# electron_v012.net
KiCad netlist of a schematic drawn in EAGLE
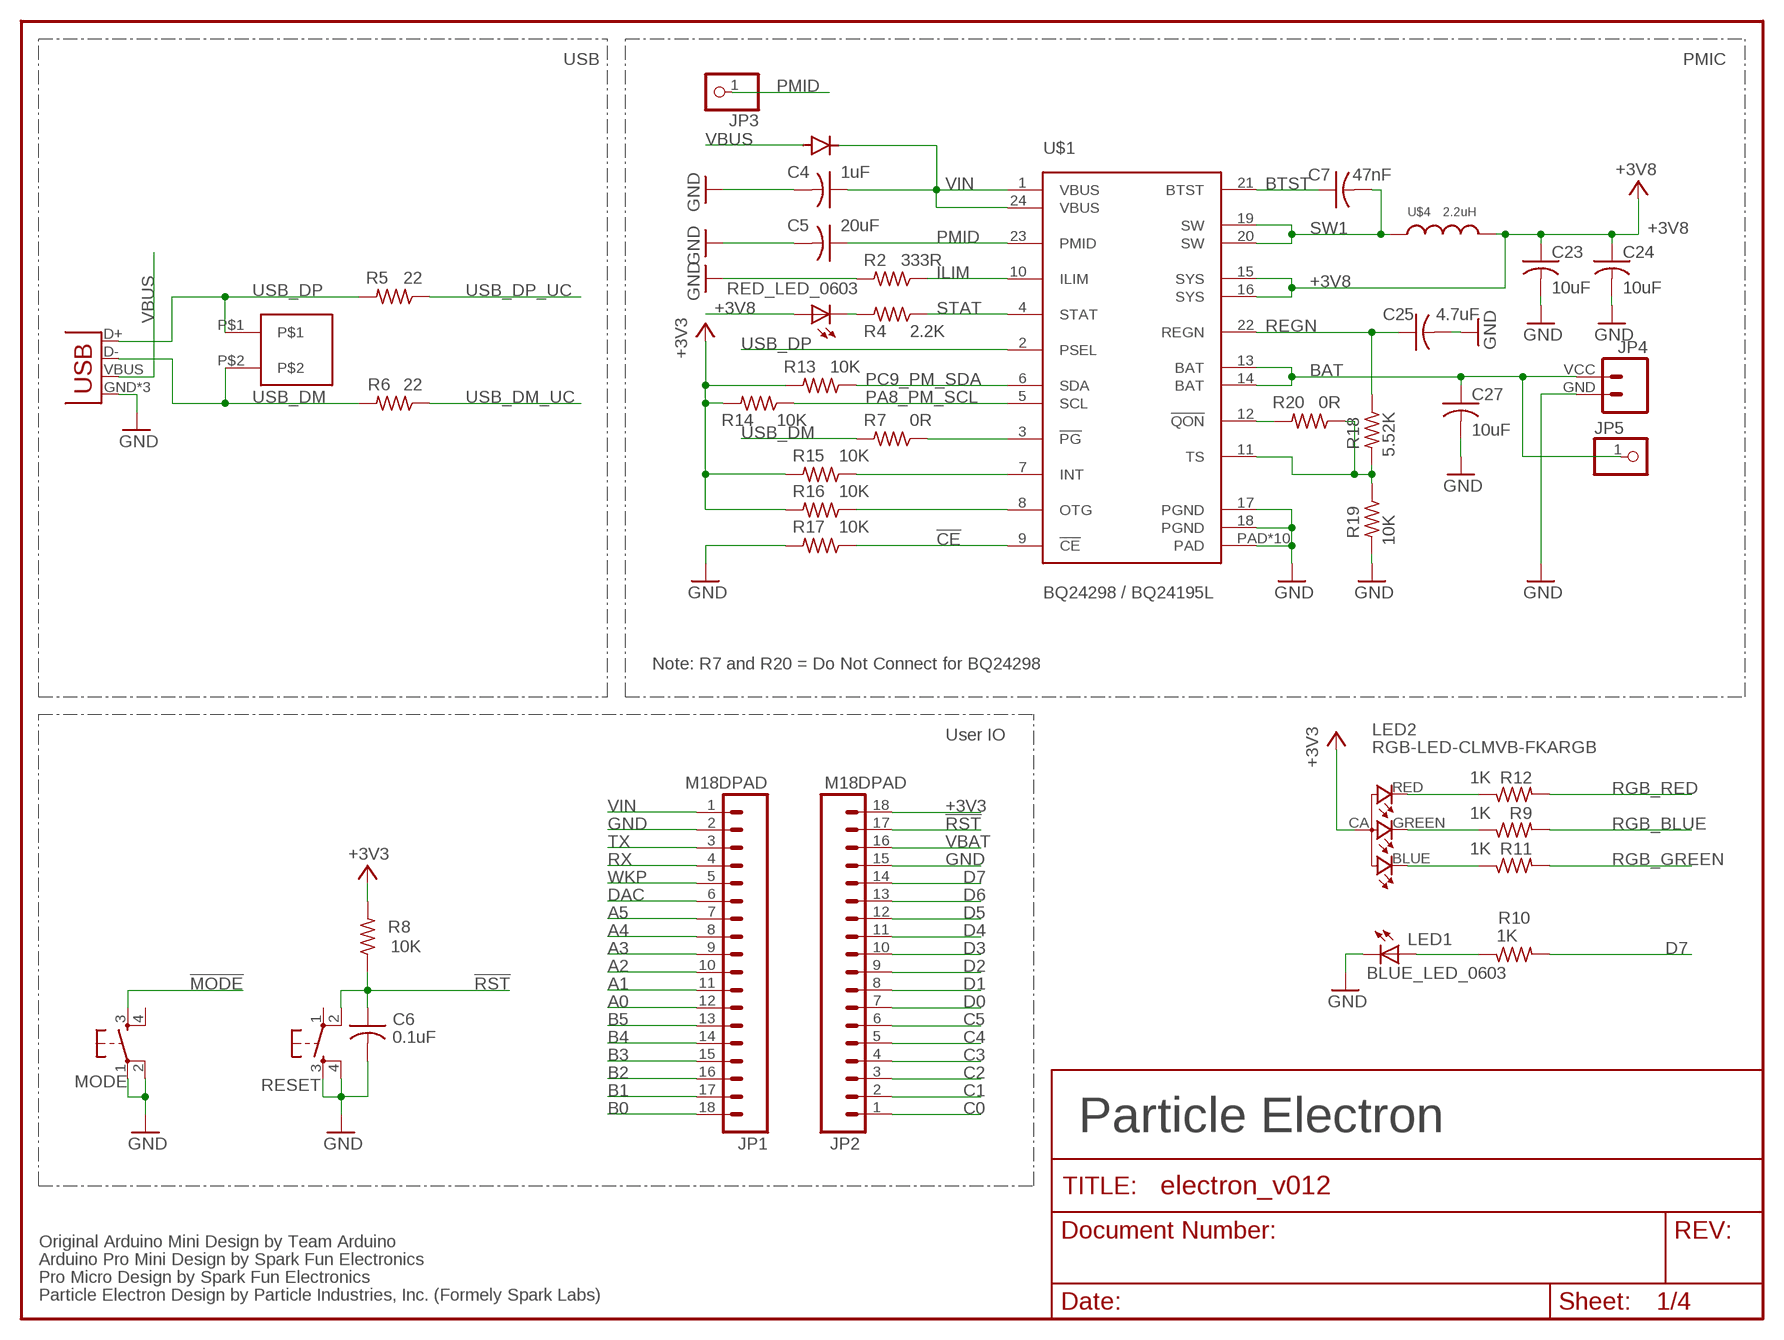
[diagram p0: schematic, sheet 1]
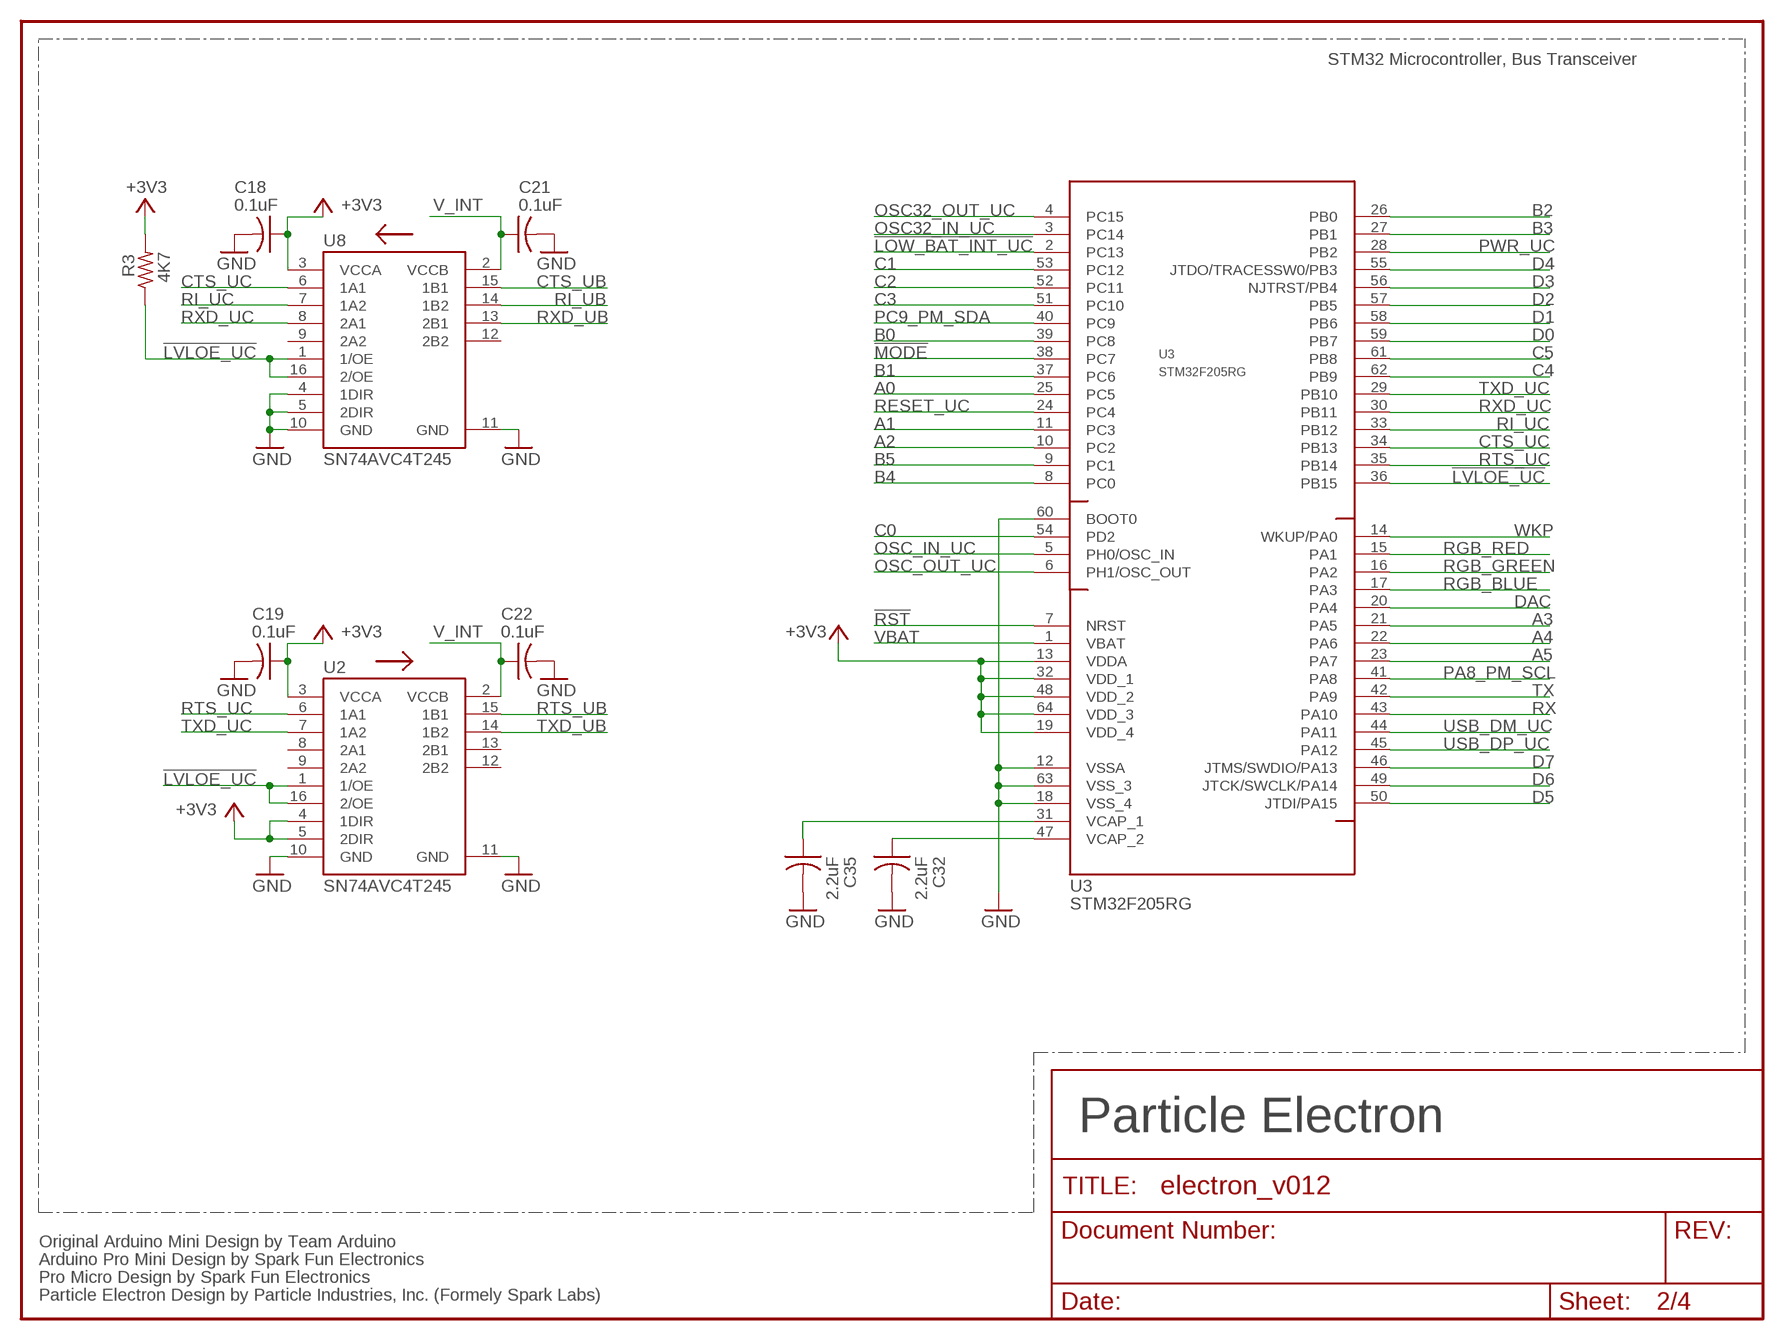
[diagram p1: schematic, sheet 2]
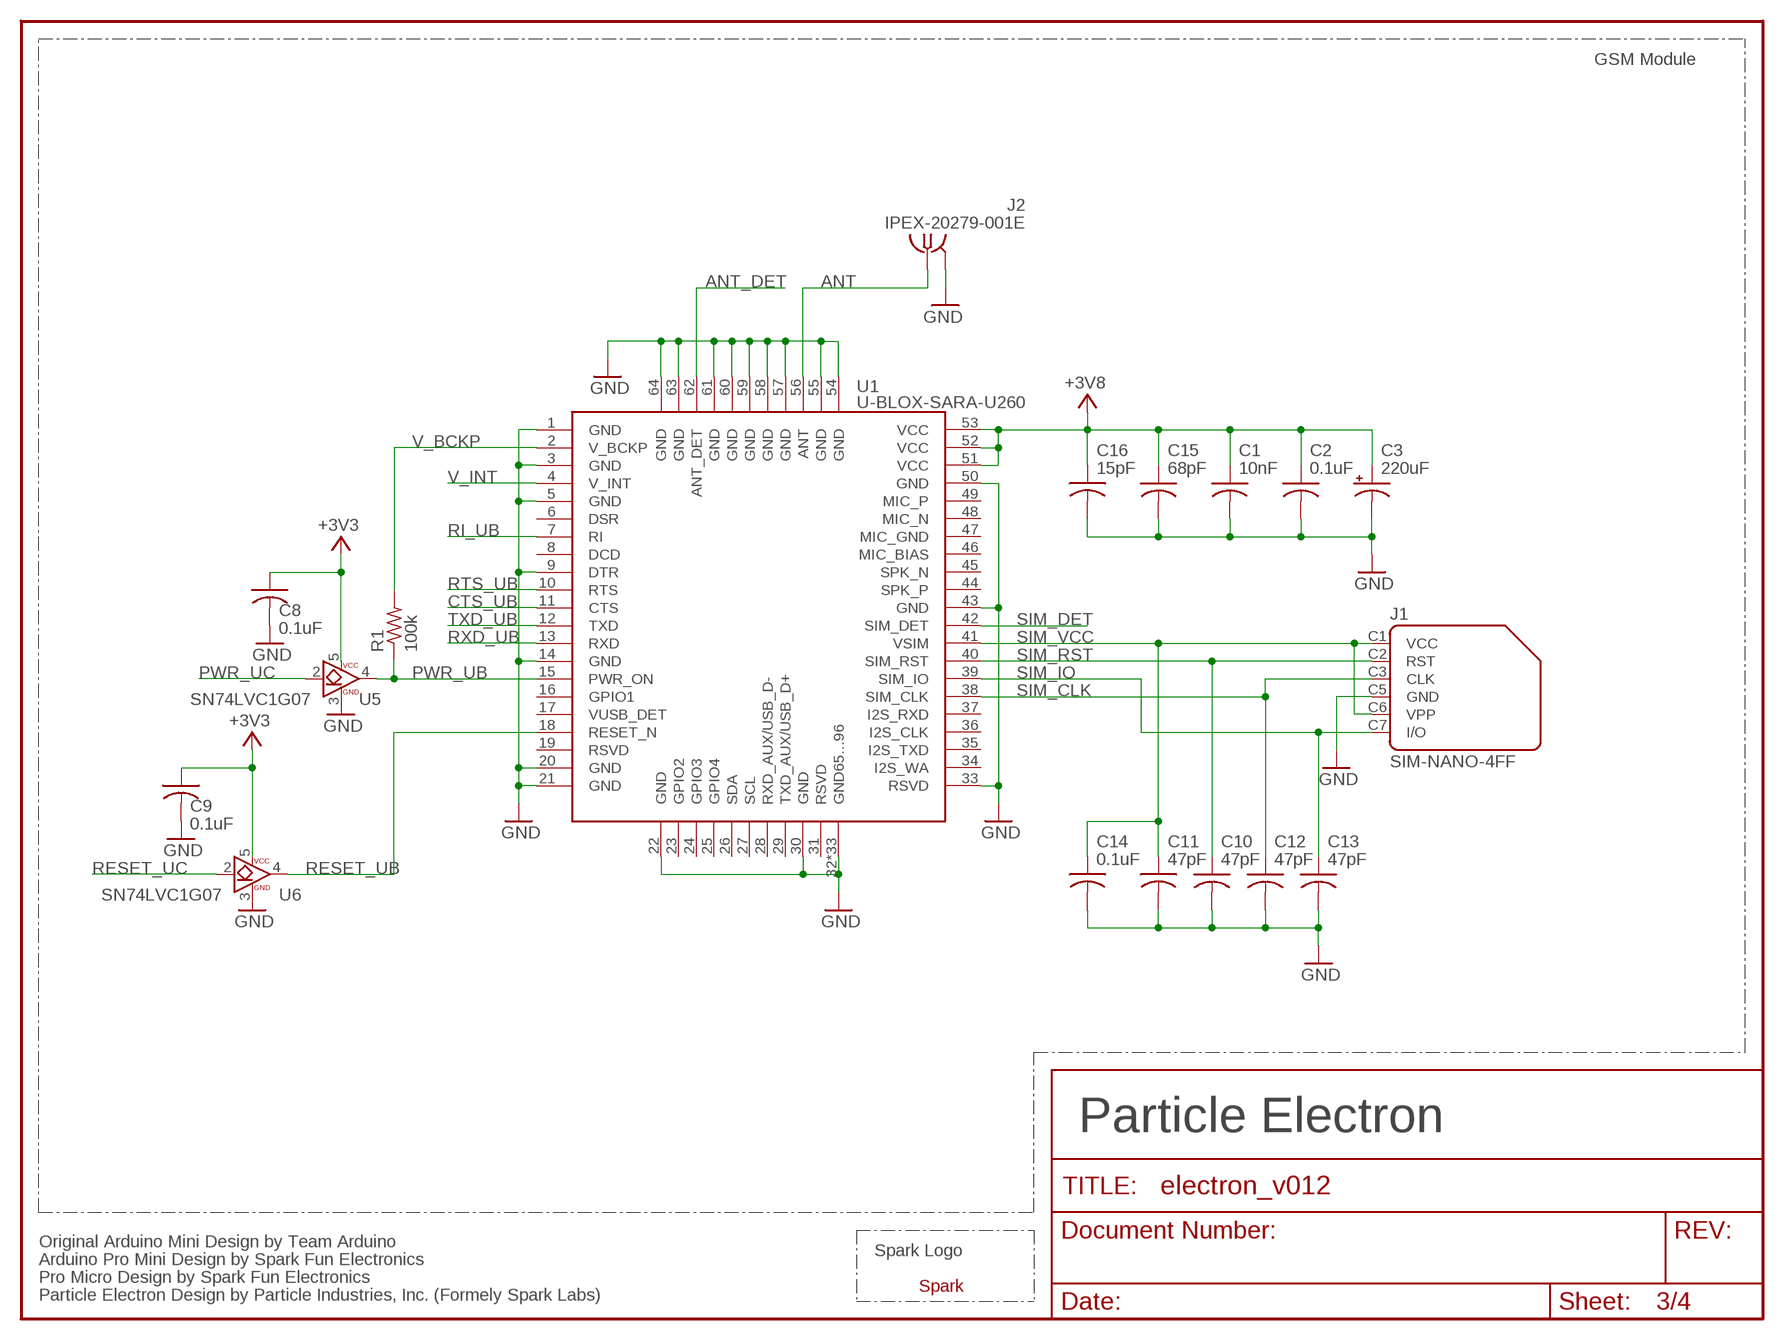
[diagram p2: schematic, sheet 3]
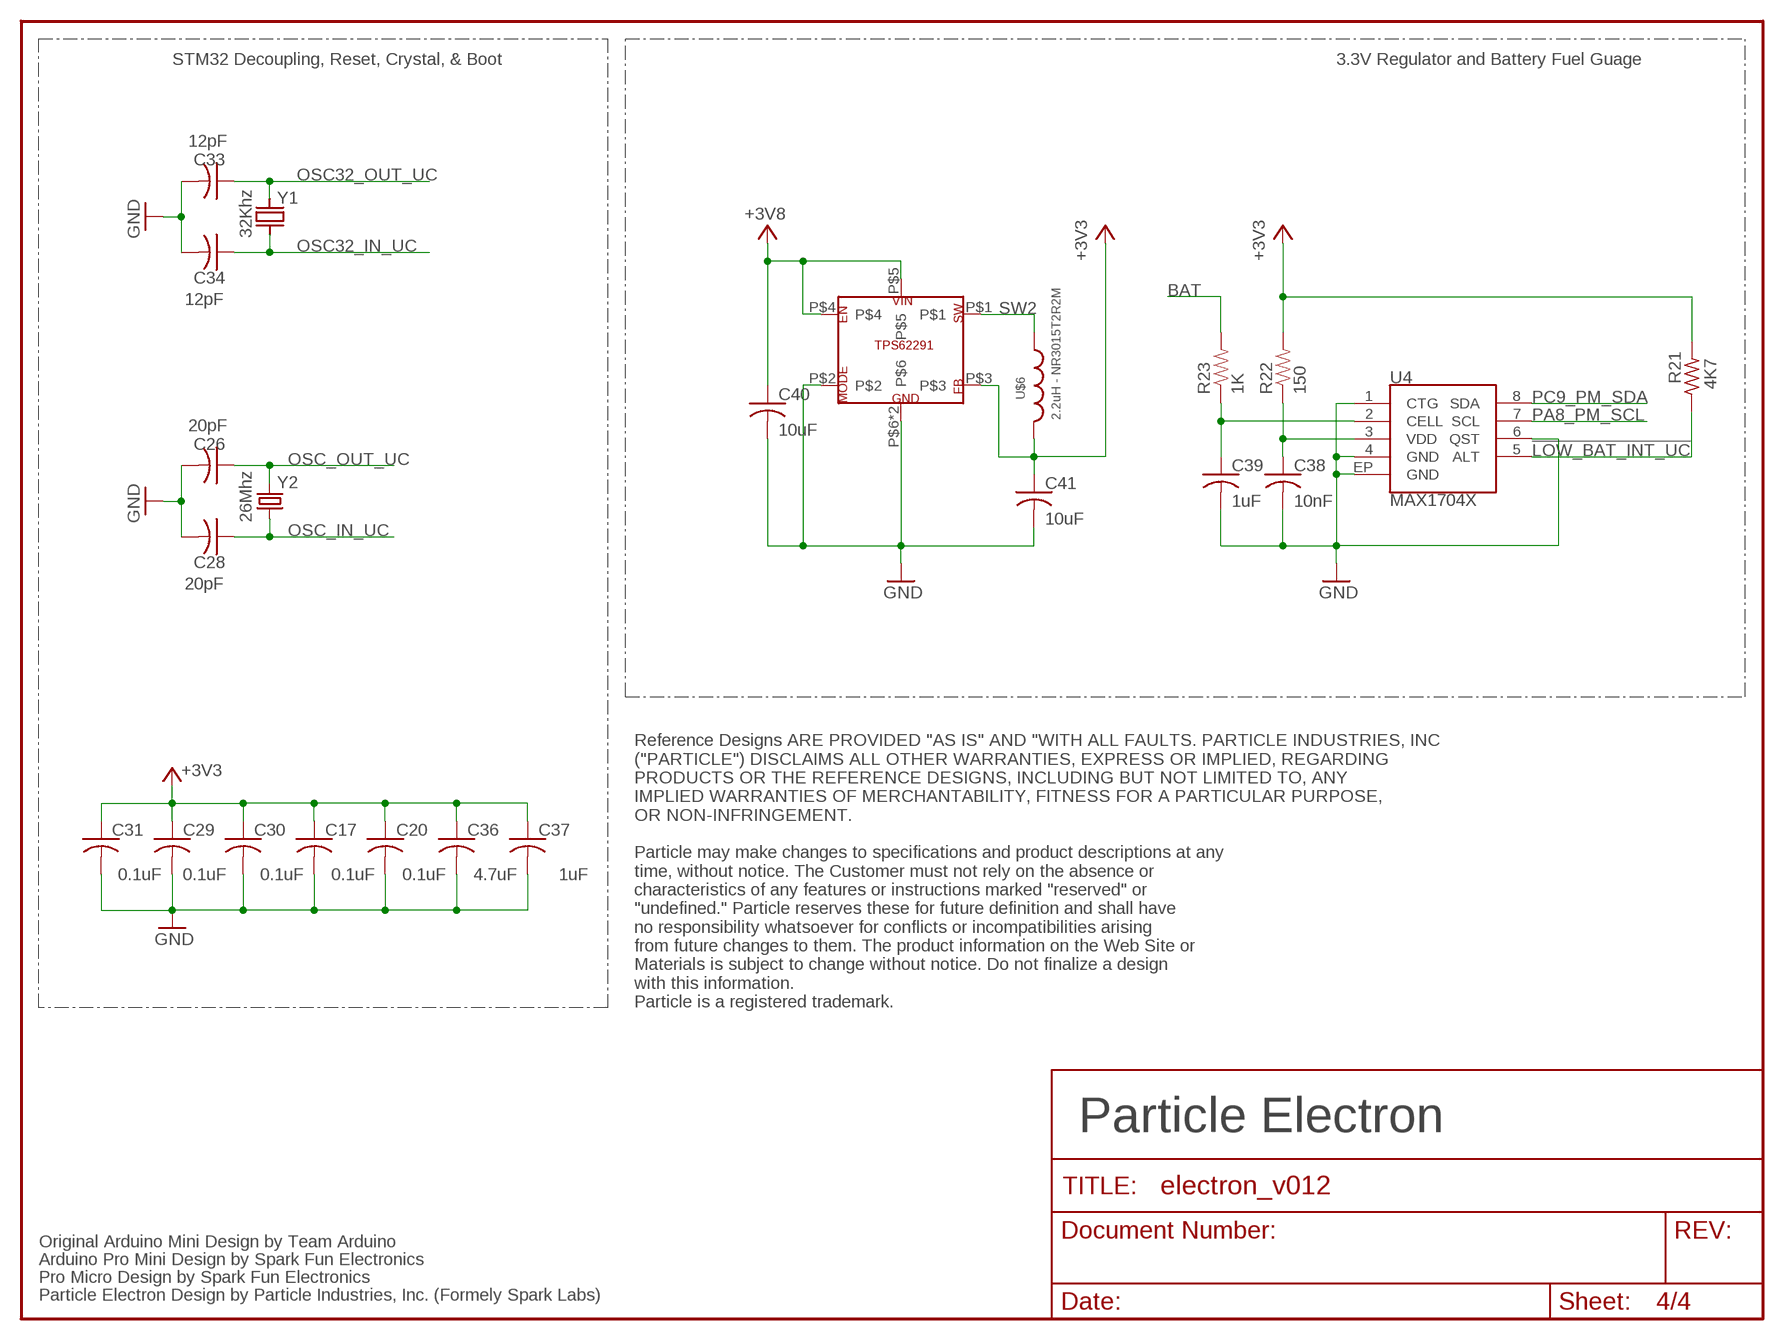
[diagram p3: schematic, sheet 4]

(export (version "E")
  (design (tool "Eeschema 10.0.6"))
  (components
    (comp (ref "C17")
      (value "0.1uF")
      (footprint "eagle-import:C0402_B")
      (libsource (lib "eagle-import") (part "C-US"))
    )
    (comp (ref "C20")
      (value "0.1uF")
      (footprint "eagle-import:C0402_B")
      (libsource (lib "eagle-import") (part "C-US"))
    )
    (comp (ref "C26")
      (value "20pF")
      (footprint "eagle-import:C0402_B")
      (libsource (lib "eagle-import") (part "C-US"))
    )
    (comp (ref "C28")
      (value "20pF")
      (footprint "eagle-import:C0402_B")
      (libsource (lib "eagle-import") (part "C-US"))
    )
    (comp (ref "C29")
      (value "0.1uF")
      (footprint "eagle-import:C0402_B")
      (libsource (lib "eagle-import") (part "C-US"))
    )
    (comp (ref "C30")
      (value "0.1uF")
      (footprint "eagle-import:C0402_B")
      (libsource (lib "eagle-import") (part "C-US"))
    )
    (comp (ref "C31")
      (value "0.1uF")
      (footprint "eagle-import:C0402_B")
      (libsource (lib "eagle-import") (part "C-US"))
    )
    (comp (ref "C33")
      (value "12pF")
      (footprint "eagle-import:C0402_B")
      (libsource (lib "eagle-import") (part "C-US"))
    )
    (comp (ref "C34")
      (value "12pF")
      (footprint "eagle-import:C0402_B")
      (libsource (lib "eagle-import") (part "C-US"))
    )
    (comp (ref "C36")
      (value "4.7uF")
      (footprint "eagle-import:C0402_B")
      (libsource (lib "eagle-import") (part "C-US"))
    )
    (comp (ref "C37")
      (value "1uF")
      (footprint "eagle-import:C0402_B")
      (libsource (lib "eagle-import") (part "C-US"))
    )
    (comp (ref "C38")
      (value "10nF")
      (footprint "eagle-import:C0402_B")
      (libsource (lib "eagle-import") (part "C-US"))
    )
    (comp (ref "C39")
      (value "1uF")
      (footprint "eagle-import:C0402_B")
      (libsource (lib "eagle-import") (part "C-US"))
    )
    (comp (ref "C40")
      (value "10uF")
      (footprint "eagle-import:C0603_B")
      (libsource (lib "eagle-import") (part "C-US0603"))
    )
    (comp (ref "C41")
      (value "10uF")
      (footprint "eagle-import:C0603_B")
      (libsource (lib "eagle-import") (part "C-US0603"))
    )
    (comp (ref "R21")
      (value "4K7")
      (footprint "eagle-import:R0402_B")
      (libsource (lib "eagle-import") (part "R-US_"))
    )
    (comp (ref "R22")
      (value "150")
      (footprint "eagle-import:0603-RES")
      (libsource (lib "eagle-import") (part "RESISTOR0603-RES"))
    )
    (comp (ref "R23")
      (value "1K")
      (footprint "eagle-import:0603-RES")
      (libsource (lib "eagle-import") (part "RESISTOR0603-RES"))
    )
    (comp (ref "U$5")
      (value "TPS62291DRV")
      (footprint "eagle-import:S-PWSON-N6")
      (libsource (lib "eagle-import") (part "TPS62291DRV"))
    )
    (comp (ref "U$6")
      (value "2.2uH - NR3015T2R2M")
      (footprint "eagle-import:INDUCTOR-NR3015")
      (libsource (lib "eagle-import") (part "INDUCTORB"))
    )
    (comp (ref "U4")
      (value "MAX1704X")
      (footprint "eagle-import:TDFN-8")
      (libsource (lib "eagle-import") (part "MAX1704X"))
    )
    (comp (ref "Y1")
      (value "32Khz")
      (footprint "eagle-import:FC135")
      (libsource (lib "eagle-import") (part "Q_FC135"))
    )
    (comp (ref "Y2")
      (value "26Mhz")
      (footprint "eagle-import:CRYSTAL-SMD-5X3")
      (libsource (lib "eagle-import") (part "CRYSTAL5X3"))
    )
    (comp (ref "BLUE_LED_0603")
      (value "LED0603")
      (footprint "eagle-import:LED-0603")
      (libsource (lib "eagle-import") (part "LED0603"))
    )
    (comp (ref "C4")
      (value "1uF")
      (footprint "eagle-import:C0603_B")
      (libsource (lib "eagle-import") (part "C-US0603"))
    )
    (comp (ref "C5")
      (value "20uF")
      (footprint "eagle-import:C0603_B")
      (libsource (lib "eagle-import") (part "C-US0603"))
    )
    (comp (ref "C6")
      (value "0.1uF")
      (footprint "eagle-import:C0402_B")
      (libsource (lib "eagle-import") (part "C-US"))
    )
    (comp (ref "C7")
      (value "47nF")
      (footprint "eagle-import:C0402_B")
      (libsource (lib "eagle-import") (part "C-US"))
    )
    (comp (ref "C23")
      (value "10uF")
      (footprint "eagle-import:C0603_B")
      (libsource (lib "eagle-import") (part "C-US0603"))
    )
    (comp (ref "C24")
      (value "10uF")
      (footprint "eagle-import:C0603_B")
      (libsource (lib "eagle-import") (part "C-US0603"))
    )
    (comp (ref "C25")
      (value "4.7uF")
      (footprint "eagle-import:C0603_B")
      (libsource (lib "eagle-import") (part "C-US0603"))
    )
    (comp (ref "C27")
      (value "10uF")
      (footprint "eagle-import:C0603_B")
      (libsource (lib "eagle-import") (part "C-US0603"))
    )
    (comp (ref "JP1")
      (value "M18DPAD")
      (footprint "eagle-import:1X18-D-PADS")
      (libsource (lib "eagle-import") (part "M18DPAD"))
    )
    (comp (ref "JP2")
      (value "M18DPAD")
      (footprint "eagle-import:1X18-D-PADS")
      (libsource (lib "eagle-import") (part "M18DPAD"))
    )
    (comp (ref "JP3")
      (value "PINHD-1X1NOSILK")
      (footprint "eagle-import:1X01_NO_SILK")
      (libsource (lib "eagle-import") (part "PINHD-1X1NOSILK"))
    )
    (comp (ref "JP4")
      (value "M024UCON-15767")
      (footprint "eagle-import:JST-2-SMD-VERT")
      (libsource (lib "eagle-import") (part "M024UCON-15767"))
    )
    (comp (ref "JP5")
      (value "PINHD-1X1NOSILK")
      (footprint "eagle-import:1X01_NO_SILK")
      (libsource (lib "eagle-import") (part "PINHD-1X1NOSILK"))
    )
    (comp (ref "LED2")
      (value "RGB-LED-CLMVB-FKARGB")
      (footprint "eagle-import:PLCC4-2MM-RGB")
      (libsource (lib "eagle-import") (part "RGB-LED-CLMVB-FKARGB"))
    )
    (comp (ref "MODE")
      (value "KMR211GLFS")
      (footprint "eagle-import:TACTILE_SWITCH_SMD")
      (libsource (lib "eagle-import") (part "TAC_SWITCHSMD"))
    )
    (comp (ref "R2")
      (value "333R")
      (footprint "eagle-import:R0402_B")
      (libsource (lib "eagle-import") (part "R-US_"))
    )
    (comp (ref "R4")
      (value "2.2K")
      (footprint "eagle-import:R0402_B")
      (libsource (lib "eagle-import") (part "R-US_"))
    )
    (comp (ref "R5")
      (value "22")
      (footprint "eagle-import:R0402_B")
      (libsource (lib "eagle-import") (part "R-US_"))
    )
    (comp (ref "R6")
      (value "22")
      (footprint "eagle-import:R0402_B")
      (libsource (lib "eagle-import") (part "R-US_"))
    )
    (comp (ref "R7")
      (value "0R")
      (footprint "eagle-import:R0402_B")
      (libsource (lib "eagle-import") (part "R-US_"))
    )
    (comp (ref "R8")
      (value "10K")
      (footprint "eagle-import:R0402_B")
      (libsource (lib "eagle-import") (part "R-US_"))
    )
    (comp (ref "R9")
      (value "1K")
      (footprint "eagle-import:R0402_B")
      (libsource (lib "eagle-import") (part "R-US_"))
    )
    (comp (ref "R10")
      (value "1K")
      (footprint "eagle-import:R0402_B")
      (libsource (lib "eagle-import") (part "R-US_"))
    )
    (comp (ref "R11")
      (value "1K")
      (footprint "eagle-import:R0402_B")
      (libsource (lib "eagle-import") (part "R-US_"))
    )
    (comp (ref "R12")
      (value "1K")
      (footprint "eagle-import:R0402_B")
      (libsource (lib "eagle-import") (part "R-US_"))
    )
    (comp (ref "R13")
      (value "10K")
      (footprint "eagle-import:R0402_B")
      (libsource (lib "eagle-import") (part "R-US_"))
    )
    (comp (ref "R14")
      (value "10K")
      (footprint "eagle-import:R0402_B")
      (libsource (lib "eagle-import") (part "R-US_"))
    )
    (comp (ref "R15")
      (value "10K")
      (footprint "eagle-import:R0402_B")
      (libsource (lib "eagle-import") (part "R-US_"))
    )
    (comp (ref "R16")
      (value "10K")
      (footprint "eagle-import:R0402_B")
      (libsource (lib "eagle-import") (part "R-US_"))
    )
    (comp (ref "R17")
      (value "10K")
      (footprint "eagle-import:R0402_B")
      (libsource (lib "eagle-import") (part "R-US_"))
    )
    (comp (ref "R18")
      (value "5.52K")
      (footprint "eagle-import:R0402_B")
      (libsource (lib "eagle-import") (part "R-US_"))
    )
    (comp (ref "R19")
      (value "10K")
      (footprint "eagle-import:R0402_B")
      (libsource (lib "eagle-import") (part "R-US_"))
    )
    (comp (ref "R20")
      (value "0R")
      (footprint "eagle-import:R0402_B")
      (libsource (lib "eagle-import") (part "R-US_"))
    )
    (comp (ref "RED_LED_0603")
      (value "LED0603")
      (footprint "eagle-import:LED-0603")
      (libsource (lib "eagle-import") (part "LED0603"))
    )
    (comp (ref "RESET")
      (value "KMR211GLFS")
      (footprint "eagle-import:TACTILE_SWITCH_SMD")
      (libsource (lib "eagle-import") (part "TAC_SWITCHSMD"))
    )
    (comp (ref "U$1")
      (value "BQ24298 / BQ24195L")
      (footprint "eagle-import:QFN24")
      (libsource (lib "eagle-import") (part "BQ24298RTWR"))
    )
    (comp (ref "U$3")
      (value "DIODE")
      (footprint "eagle-import:DIODE-DO-220AA(SMP)")
      (libsource (lib "eagle-import") (part "DIODE"))
    )
    (comp (ref "U$4")
      (value "2.2uH")
      (footprint "eagle-import:INDUCTOR-4020")
      (libsource (lib "eagle-import") (part "INDUCTORH"))
    )
    (comp (ref "U$7")
      (value "M02_0.05_HEADER")
      (footprint "eagle-import:M02_0.05_HEADER")
      (libsource (lib "eagle-import") (part "M02_0.05_HEADER"))
    )
    (comp (ref "X1")
      (value "USB-MICROB")
      (footprint "eagle-import:USB-MICROB-SLOT-HOLE")
      (libsource (lib "eagle-import") (part "USBUSB-MICROB-SLOT-HOLE"))
    )
    (comp (ref "C1")
      (value "10nF")
      (footprint "eagle-import:C0402_B")
      (libsource (lib "eagle-import") (part "C-US"))
    )
    (comp (ref "C2")
      (value "0.1uF")
      (footprint "eagle-import:C0402_B")
      (libsource (lib "eagle-import") (part "C-US"))
    )
    (comp (ref "C3")
      (value "220uF")
      (footprint "eagle-import:C_6032-28R")
      (libsource (lib "eagle-import") (part "CPOL-USC/6032-28R"))
    )
    (comp (ref "C8")
      (value "0.1uF")
      (footprint "eagle-import:C0402_B")
      (libsource (lib "eagle-import") (part "C-US"))
    )
    (comp (ref "C9")
      (value "0.1uF")
      (footprint "eagle-import:C0402_B")
      (libsource (lib "eagle-import") (part "C-US"))
    )
    (comp (ref "C10")
      (value "47pF")
      (footprint "eagle-import:C0402_B")
      (libsource (lib "eagle-import") (part "C-US"))
    )
    (comp (ref "C11")
      (value "47pF")
      (footprint "eagle-import:C0402_B")
      (libsource (lib "eagle-import") (part "C-US"))
    )
    (comp (ref "C12")
      (value "47pF")
      (footprint "eagle-import:C0402_B")
      (libsource (lib "eagle-import") (part "C-US"))
    )
    (comp (ref "C13")
      (value "47pF")
      (footprint "eagle-import:C0402_B")
      (libsource (lib "eagle-import") (part "C-US"))
    )
    (comp (ref "C14")
      (value "0.1uF")
      (footprint "eagle-import:C0402_B")
      (libsource (lib "eagle-import") (part "C-US"))
    )
    (comp (ref "C15")
      (value "68pF")
      (footprint "eagle-import:C0402_B")
      (libsource (lib "eagle-import") (part "C-US"))
    )
    (comp (ref "C16")
      (value "15pF")
      (footprint "eagle-import:C0402_B")
      (libsource (lib "eagle-import") (part "C-US"))
    )
    (comp (ref "J1")
      (value "SIM-NANO-4FF")
      (footprint "eagle-import:GCT-SIM8100")
      (libsource (lib "eagle-import") (part "SIM-NANO-4FF"))
    )
    (comp (ref "J2")
      (value "IPEX-20279-001E")
      (footprint "eagle-import:IPEX-20279-001E")
      (libsource (lib "eagle-import") (part "IPEX-20279-001E"))
    )
    (comp (ref "R1")
      (value "100k")
      (footprint "eagle-import:R0402_B")
      (libsource (lib "eagle-import") (part "R-US_"))
    )
    (comp (ref "U$2")
      (value "SPARK_LOGO2")
      (footprint "eagle-import:SPARK_LOGO2")
      (libsource (lib "eagle-import") (part "SPARK_LOGO2"))
    )
    (comp (ref "U1")
      (value "U-BLOX-SARA-U260")
      (footprint "eagle-import:U-BLOX-SARA-U2")
      (libsource (lib "eagle-import") (part "U-BLOX-SARA-U260"))
    )
    (comp (ref "U5")
      (value "SN74LVC1G07")
      (footprint "eagle-import:SC-70-5")
      (libsource (lib "eagle-import") (part "SN74LVC1G07"))
    )
    (comp (ref "U6")
      (value "SN74LVC1G07")
      (footprint "eagle-import:SC-70-5")
      (libsource (lib "eagle-import") (part "SN74LVC1G07"))
    )
    (comp (ref "C18")
      (value "0.1uF")
      (footprint "eagle-import:C0402_B")
      (libsource (lib "eagle-import") (part "C-US"))
    )
    (comp (ref "C19")
      (value "0.1uF")
      (footprint "eagle-import:C0402_B")
      (libsource (lib "eagle-import") (part "C-US"))
    )
    (comp (ref "C21")
      (value "0.1uF")
      (footprint "eagle-import:C0402_B")
      (libsource (lib "eagle-import") (part "C-US"))
    )
    (comp (ref "C22")
      (value "0.1uF")
      (footprint "eagle-import:C0402_B")
      (libsource (lib "eagle-import") (part "C-US"))
    )
    (comp (ref "C32")
      (value "2.2uF")
      (footprint "eagle-import:C0402_B")
      (libsource (lib "eagle-import") (part "C-US"))
    )
    (comp (ref "C35")
      (value "2.2uF")
      (footprint "eagle-import:C0402_B")
      (libsource (lib "eagle-import") (part "C-US"))
    )
    (comp (ref "R3")
      (value "4K7")
      (footprint "eagle-import:R0402_B")
      (libsource (lib "eagle-import") (part "R-US_"))
    )
    (comp (ref "U2")
      (value "SN74AVC4T245")
      (footprint "eagle-import:UFQFN-16")
      (libsource (lib "eagle-import") (part "SN74AVC4T245"))
    )
    (comp (ref "U3")
      (value "STM32F205RG")
      (footprint "eagle-import:LQFP64")
      (libsource (lib "eagle-import") (part "STM32F20XR"))
    )
    (comp (ref "U8")
      (value "SN74AVC4T245")
      (footprint "eagle-import:UFQFN-16")
      (libsource (lib "eagle-import") (part "SN74AVC4T245"))
    )
  )
  (nets
    (net (code "1") (name "+3V3") (class "Default")
      (node (ref "C17") (pin "1") (pinfunction "1_1") (pintype "passive"))
      (node (ref "C18") (pin "1") (pinfunction "1_1") (pintype "passive"))
      (node (ref "C19") (pin "1") (pinfunction "1_1") (pintype "passive"))
      (node (ref "C20") (pin "1") (pinfunction "1_1") (pintype "passive"))
      (node (ref "C29") (pin "1") (pinfunction "1_1") (pintype "passive"))
      (node (ref "C30") (pin "1") (pinfunction "1_1") (pintype "passive"))
      (node (ref "C31") (pin "1") (pinfunction "1_1") (pintype "passive"))
      (node (ref "C36") (pin "1") (pinfunction "1_1") (pintype "passive"))
      (node (ref "C37") (pin "1") (pinfunction "1_1") (pintype "passive"))
      (node (ref "C41") (pin "1") (pinfunction "1_1") (pintype "passive"))
      (node (ref "C8") (pin "1") (pinfunction "1_1") (pintype "passive"))
      (node (ref "C9") (pin "1") (pinfunction "1_1") (pintype "passive"))
      (node (ref "JP2") (pin "18") (pinfunction "18_18") (pintype "passive"))
      (node (ref "LED2") (pin "CA") (pinfunction "1_CA") (pintype "passive"))
      (node (ref "R13") (pin "2") (pinfunction "2_2") (pintype "passive"))
      (node (ref "R14") (pin "2") (pinfunction "2_2") (pintype "passive"))
      (node (ref "R15") (pin "2") (pinfunction "2_2") (pintype "passive"))
      (node (ref "R16") (pin "2") (pinfunction "2_2") (pintype "passive"))
      (node (ref "R21") (pin "2") (pinfunction "2_2") (pintype "passive"))
      (node (ref "R22") (pin "2") (pinfunction "2_2") (pintype "passive"))
      (node (ref "R3") (pin "2") (pinfunction "2_2") (pintype "passive"))
      (node (ref "R8") (pin "2") (pinfunction "2_2") (pintype "passive"))
      (node (ref "U$5") (pin "P$3") (pinfunction "P$3_P$3") (pintype "bidirectional"))
      (node (ref "U$6") (pin "2") (pinfunction "2_2") (pintype "passive"))
      (node (ref "U2") (pin "3") (pinfunction "VCCA_3") (pintype "bidirectional"))
      (node (ref "U2") (pin "4") (pinfunction "1DIR_4") (pintype "bidirectional"))
      (node (ref "U2") (pin "5") (pinfunction "2DIR_5") (pintype "bidirectional"))
      (node (ref "U3") (pin "13") (pinfunction "VDDA_13") (pintype "power_in"))
      (node (ref "U3") (pin "19") (pinfunction "VDD_4_19") (pintype "power_in"))
      (node (ref "U3") (pin "32") (pinfunction "VDD_1_32") (pintype "power_in"))
      (node (ref "U3") (pin "48") (pinfunction "VDD_2_48") (pintype "power_in"))
      (node (ref "U3") (pin "64") (pinfunction "VDD_3_64") (pintype "power_in"))
      (node (ref "U5") (pin "5") (pinfunction "VCC_5") (pintype "bidirectional"))
      (node (ref "U6") (pin "5") (pinfunction "VCC_5") (pintype "bidirectional"))
      (node (ref "U8") (pin "3") (pinfunction "VCCA_3") (pintype "bidirectional"))
    )
    (net (code "2") (name "+3V8") (class "Default")
      (node (ref "C1") (pin "1") (pinfunction "1_1") (pintype "passive"))
      (node (ref "C15") (pin "1") (pinfunction "1_1") (pintype "passive"))
      (node (ref "C16") (pin "1") (pinfunction "1_1") (pintype "passive"))
      (node (ref "C2") (pin "1") (pinfunction "1_1") (pintype "passive"))
      (node (ref "C23") (pin "1") (pinfunction "1_1") (pintype "passive"))
      (node (ref "C24") (pin "1") (pinfunction "1_1") (pintype "passive"))
      (node (ref "C3") (pin "+") (pinfunction "+_+") (pintype "passive"))
      (node (ref "C40") (pin "1") (pinfunction "1_1") (pintype "passive"))
      (node (ref "RED_LED_0603") (pin "A") (pinfunction "A_A") (pintype "passive"))
      (node (ref "U$1") (pin "15") (pinfunction "SYS_15") (pintype "power_in"))
      (node (ref "U$1") (pin "16") (pinfunction "SYS_16") (pintype "power_in"))
      (node (ref "U$4") (pin "P$2") (pinfunction "2_P$2") (pintype "passive"))
      (node (ref "U$5") (pin "P$4") (pinfunction "P$4_P$4") (pintype "bidirectional"))
      (node (ref "U$5") (pin "P$5") (pinfunction "P$5_P$5") (pintype "bidirectional"))
      (node (ref "U1") (pin "51") (pinfunction "VCC_51") (pintype "bidirectional"))
      (node (ref "U1") (pin "52") (pinfunction "VCC_52") (pintype "bidirectional"))
      (node (ref "U1") (pin "53") (pinfunction "VCC_53") (pintype "bidirectional"))
    )
    (net (code "3") (name "A0") (class "Default")
      (node (ref "JP1") (pin "12") (pinfunction "12_12") (pintype "passive"))
      (node (ref "U3") (pin "25") (pinfunction "PC5_25") (pintype "bidirectional"))
    )
    (net (code "4") (name "A1") (class "Default")
      (node (ref "JP1") (pin "11") (pinfunction "11_11") (pintype "passive"))
      (node (ref "U3") (pin "11") (pinfunction "PC3_11") (pintype "bidirectional"))
    )
    (net (code "5") (name "A2") (class "Default")
      (node (ref "JP1") (pin "10") (pinfunction "10_10") (pintype "passive"))
      (node (ref "U3") (pin "10") (pinfunction "PC2_10") (pintype "bidirectional"))
    )
    (net (code "6") (name "A3") (class "Default")
      (node (ref "JP1") (pin "9") (pinfunction "9_9") (pintype "passive"))
      (node (ref "U3") (pin "21") (pinfunction "PA5_21") (pintype "bidirectional"))
    )
    (net (code "7") (name "A4") (class "Default")
      (node (ref "JP1") (pin "8") (pinfunction "8_8") (pintype "passive"))
      (node (ref "U3") (pin "22") (pinfunction "PA6_22") (pintype "bidirectional"))
    )
    (net (code "8") (name "A5") (class "Default")
      (node (ref "JP1") (pin "7") (pinfunction "7_7") (pintype "passive"))
      (node (ref "U3") (pin "23") (pinfunction "PA7_23") (pintype "bidirectional"))
    )
    (net (code "9") (name "ANT") (class "Default")
      (node (ref "J2") (pin "1") (pinfunction "1_1") (pintype "passive"))
      (node (ref "U1") (pin "56") (pinfunction "ANT_56") (pintype "bidirectional"))
    )
    (net (code "10") (name "ANT_DET") (class "Default")
      (node (ref "U1") (pin "62") (pinfunction "ANT_DET_62") (pintype "bidirectional"))
    )
    (net (code "11") (name "B0") (class "Default")
      (node (ref "JP1") (pin "18") (pinfunction "18_18") (pintype "passive"))
      (node (ref "U3") (pin "39") (pinfunction "PC8_39") (pintype "bidirectional"))
    )
    (net (code "12") (name "B1") (class "Default")
      (node (ref "JP1") (pin "17") (pinfunction "17_17") (pintype "passive"))
      (node (ref "U3") (pin "37") (pinfunction "PC6_37") (pintype "bidirectional"))
    )
    (net (code "13") (name "B2") (class "Default")
      (node (ref "JP1") (pin "16") (pinfunction "16_16") (pintype "passive"))
      (node (ref "U3") (pin "26") (pinfunction "PB0_26") (pintype "bidirectional"))
    )
    (net (code "14") (name "B3") (class "Default")
      (node (ref "JP1") (pin "15") (pinfunction "15_15") (pintype "passive"))
      (node (ref "U3") (pin "27") (pinfunction "PB1_27") (pintype "bidirectional"))
    )
    (net (code "15") (name "B4") (class "Default")
      (node (ref "JP1") (pin "14") (pinfunction "14_14") (pintype "passive"))
      (node (ref "U3") (pin "8") (pinfunction "PC0_8") (pintype "bidirectional"))
    )
    (net (code "16") (name "B5") (class "Default")
      (node (ref "JP1") (pin "13") (pinfunction "13_13") (pintype "passive"))
      (node (ref "U3") (pin "9") (pinfunction "PC1_9") (pintype "bidirectional"))
    )
    (net (code "17") (name "BAT") (class "Default")
      (node (ref "C27") (pin "1") (pinfunction "1_1") (pintype "passive"))
      (node (ref "JP4") (pin "VCC") (pinfunction "2_VCC") (pintype "passive"))
      (node (ref "JP5") (pin "1") (pinfunction "1_1") (pintype "passive"))
      (node (ref "R23") (pin "2") (pinfunction "2_2") (pintype "passive"))
      (node (ref "U$1") (pin "13") (pinfunction "BAT_13") (pintype "passive"))
      (node (ref "U$1") (pin "14") (pinfunction "BAT_14") (pintype "power_in"))
    )
    (net (code "18") (name "BTST") (class "Default")
      (node (ref "C7") (pin "1") (pinfunction "1_1") (pintype "passive"))
      (node (ref "U$1") (pin "21") (pinfunction "BTST_21") (pintype "bidirectional"))
    )
    (net (code "19") (name "C0") (class "Default")
      (node (ref "JP2") (pin "1") (pinfunction "1_1") (pintype "passive"))
      (node (ref "U3") (pin "54") (pinfunction "PD2_54") (pintype "bidirectional"))
    )
    (net (code "20") (name "C1") (class "Default")
      (node (ref "JP2") (pin "2") (pinfunction "2_2") (pintype "passive"))
      (node (ref "U3") (pin "53") (pinfunction "PC12_53") (pintype "bidirectional"))
    )
    (net (code "21") (name "C2") (class "Default")
      (node (ref "JP2") (pin "3") (pinfunction "3_3") (pintype "passive"))
      (node (ref "U3") (pin "52") (pinfunction "PC11_52") (pintype "bidirectional"))
    )
    (net (code "22") (name "C3") (class "Default")
      (node (ref "JP2") (pin "4") (pinfunction "4_4") (pintype "passive"))
      (node (ref "U3") (pin "51") (pinfunction "PC10_51") (pintype "bidirectional"))
    )
    (net (code "23") (name "C4") (class "Default")
      (node (ref "JP2") (pin "5") (pinfunction "5_5") (pintype "passive"))
      (node (ref "U3") (pin "62") (pinfunction "PB9_62") (pintype "bidirectional"))
    )
    (net (code "24") (name "C5") (class "Default")
      (node (ref "JP2") (pin "6") (pinfunction "6_6") (pintype "passive"))
      (node (ref "U3") (pin "61") (pinfunction "PB8_61") (pintype "bidirectional"))
    )
    (net (code "25") (name "CTS_UB") (class "Default")
      (node (ref "U1") (pin "11") (pinfunction "CTS_11") (pintype "bidirectional"))
      (node (ref "U8") (pin "15") (pinfunction "1B1_15") (pintype "bidirectional"))
    )
    (net (code "26") (name "CTS_UC") (class "Default")
      (node (ref "U3") (pin "34") (pinfunction "PB13_34") (pintype "bidirectional"))
      (node (ref "U8") (pin "6") (pinfunction "1A1_6") (pintype "bidirectional"))
    )
    (net (code "27") (name "D0") (class "Default")
      (node (ref "JP2") (pin "7") (pinfunction "7_7") (pintype "passive"))
      (node (ref "U3") (pin "59") (pinfunction "PB7_59") (pintype "bidirectional"))
    )
    (net (code "28") (name "D1") (class "Default")
      (node (ref "JP2") (pin "8") (pinfunction "8_8") (pintype "passive"))
      (node (ref "U3") (pin "58") (pinfunction "PB6_58") (pintype "bidirectional"))
    )
    (net (code "29") (name "D2") (class "Default")
      (node (ref "JP2") (pin "9") (pinfunction "9_9") (pintype "passive"))
      (node (ref "U3") (pin "57") (pinfunction "PB5_57") (pintype "bidirectional"))
    )
    (net (code "30") (name "D3") (class "Default")
      (node (ref "JP2") (pin "10") (pinfunction "10_10") (pintype "passive"))
      (node (ref "U3") (pin "56") (pinfunction "NJTRST/PB4_56") (pintype "bidirectional"))
    )
    (net (code "31") (name "D4") (class "Default")
      (node (ref "JP2") (pin "11") (pinfunction "11_11") (pintype "passive"))
      (node (ref "U3") (pin "55") (pinfunction "JTDO/TRACESSW0/PB3_55") (pintype "bidirectional"))
    )
    (net (code "32") (name "D5") (class "Default")
      (node (ref "JP2") (pin "12") (pinfunction "12_12") (pintype "passive"))
      (node (ref "U3") (pin "50") (pinfunction "JTDI/PA15_50") (pintype "bidirectional"))
    )
    (net (code "33") (name "D6") (class "Default")
      (node (ref "JP2") (pin "13") (pinfunction "13_13") (pintype "passive"))
      (node (ref "U3") (pin "49") (pinfunction "JTCK/SWCLK/PA14_49") (pintype "bidirectional"))
    )
    (net (code "34") (name "D7") (class "Default")
      (node (ref "JP2") (pin "14") (pinfunction "14_14") (pintype "passive"))
      (node (ref "R10") (pin "2") (pinfunction "2_2") (pintype "passive"))
      (node (ref "U3") (pin "46") (pinfunction "JTMS/SWDIO/PA13_46") (pintype "bidirectional"))
    )
    (net (code "35") (name "DAC") (class "Default")
      (node (ref "JP1") (pin "6") (pinfunction "6_6") (pintype "passive"))
      (node (ref "U3") (pin "20") (pinfunction "PA4_20") (pintype "bidirectional"))
    )
    (net (code "36") (name "GND") (class "Default")
      (node (ref "BLUE_LED_0603") (pin "C") (pinfunction "C_C") (pintype "passive"))
      (node (ref "C1") (pin "2") (pinfunction "2_2") (pintype "passive"))
      (node (ref "C10") (pin "2") (pinfunction "2_2") (pintype "passive"))
      (node (ref "C11") (pin "2") (pinfunction "2_2") (pintype "passive"))
      (node (ref "C12") (pin "2") (pinfunction "2_2") (pintype "passive"))
      (node (ref "C13") (pin "2") (pinfunction "2_2") (pintype "passive"))
      (node (ref "C14") (pin "2") (pinfunction "2_2") (pintype "passive"))
      (node (ref "C15") (pin "2") (pinfunction "2_2") (pintype "passive"))
      (node (ref "C16") (pin "2") (pinfunction "2_2") (pintype "passive"))
      (node (ref "C17") (pin "2") (pinfunction "2_2") (pintype "passive"))
      (node (ref "C18") (pin "2") (pinfunction "2_2") (pintype "passive"))
      (node (ref "C19") (pin "2") (pinfunction "2_2") (pintype "passive"))
      (node (ref "C2") (pin "2") (pinfunction "2_2") (pintype "passive"))
      (node (ref "C20") (pin "2") (pinfunction "2_2") (pintype "passive"))
      (node (ref "C21") (pin "2") (pinfunction "2_2") (pintype "passive"))
      (node (ref "C22") (pin "2") (pinfunction "2_2") (pintype "passive"))
      (node (ref "C23") (pin "2") (pinfunction "2_2") (pintype "passive"))
      (node (ref "C24") (pin "2") (pinfunction "2_2") (pintype "passive"))
      (node (ref "C25") (pin "2") (pinfunction "2_2") (pintype "passive"))
      (node (ref "C26") (pin "2") (pinfunction "2_2") (pintype "passive"))
      (node (ref "C27") (pin "2") (pinfunction "2_2") (pintype "passive"))
      (node (ref "C28") (pin "2") (pinfunction "2_2") (pintype "passive"))
      (node (ref "C29") (pin "2") (pinfunction "2_2") (pintype "passive"))
      (node (ref "C3") (pin "-") (pinfunction "-_-") (pintype "passive"))
      (node (ref "C30") (pin "2") (pinfunction "2_2") (pintype "passive"))
      (node (ref "C31") (pin "2") (pinfunction "2_2") (pintype "passive"))
      (node (ref "C32") (pin "2") (pinfunction "2_2") (pintype "passive"))
      (node (ref "C33") (pin "2") (pinfunction "2_2") (pintype "passive"))
      (node (ref "C34") (pin "2") (pinfunction "2_2") (pintype "passive"))
      (node (ref "C35") (pin "2") (pinfunction "2_2") (pintype "passive"))
      (node (ref "C36") (pin "2") (pinfunction "2_2") (pintype "passive"))
      (node (ref "C37") (pin "2") (pinfunction "2_2") (pintype "passive"))
      (node (ref "C38") (pin "2") (pinfunction "2_2") (pintype "passive"))
      (node (ref "C39") (pin "2") (pinfunction "2_2") (pintype "passive"))
      (node (ref "C4") (pin "2") (pinfunction "2_2") (pintype "passive"))
      (node (ref "C40") (pin "2") (pinfunction "2_2") (pintype "passive"))
      (node (ref "C41") (pin "2") (pinfunction "2_2") (pintype "passive"))
      (node (ref "C5") (pin "2") (pinfunction "2_2") (pintype "passive"))
      (node (ref "C6") (pin "2") (pinfunction "2_2") (pintype "passive"))
      (node (ref "C8") (pin "2") (pinfunction "2_2") (pintype "passive"))
      (node (ref "C9") (pin "2") (pinfunction "2_2") (pintype "passive"))
      (node (ref "J1") (pin "C5") (pinfunction "GND_C5") (pintype "passive"))
      (node (ref "J2") (pin "2@1") (pinfunction "GND_2@1") (pintype "passive"))
      (node (ref "J2") (pin "2@2") (pinfunction "GND_2@2") (pintype "passive"))
      (node (ref "JP1") (pin "2") (pinfunction "2_2") (pintype "passive"))
      (node (ref "JP2") (pin "15") (pinfunction "15_15") (pintype "passive"))
      (node (ref "JP4") (pin "GND") (pinfunction "1_GND") (pintype "passive"))
      (node (ref "MODE") (pin "1") (pinfunction "1_1") (pintype "passive"))
      (node (ref "MODE") (pin "2") (pinfunction "2_2") (pintype "passive"))
      (node (ref "R17") (pin "2") (pinfunction "2_2") (pintype "passive"))
      (node (ref "R19") (pin "2") (pinfunction "2_2") (pintype "passive"))
      (node (ref "R2") (pin "2") (pinfunction "2_2") (pintype "passive"))
      (node (ref "RESET") (pin "3") (pinfunction "3_3") (pintype "passive"))
      (node (ref "RESET") (pin "4") (pinfunction "4_4") (pintype "passive"))
      (node (ref "U$1") (pin "17") (pinfunction "PGND_17") (pintype "passive"))
      (node (ref "U$1") (pin "18") (pinfunction "PGND_18") (pintype "passive"))
      (node (ref "U$1") (pin "PAD") (pinfunction "PAD_PAD") (pintype "power_in"))
      (node (ref "U$1") (pin "PAD@1") (pinfunction "PAD_PAD@1") (pintype "power_in"))
      (node (ref "U$1") (pin "PAD@2") (pinfunction "PAD_PAD@2") (pintype "power_in"))
      (node (ref "U$1") (pin "PAD@3") (pinfunction "PAD_PAD@3") (pintype "power_in"))
      (node (ref "U$1") (pin "PAD@4") (pinfunction "PAD_PAD@4") (pintype "power_in"))
      (node (ref "U$1") (pin "PAD@5") (pinfunction "PAD_PAD@5") (pintype "power_in"))
      (node (ref "U$1") (pin "PAD@6") (pinfunction "PAD_PAD@6") (pintype "power_in"))
      (node (ref "U$1") (pin "PAD@7") (pinfunction "PAD_PAD@7") (pintype "power_in"))
      (node (ref "U$1") (pin "PAD@8") (pinfunction "PAD_PAD@8") (pintype "power_in"))
      (node (ref "U$1") (pin "PAD@9") (pinfunction "PAD_PAD@9") (pintype "power_in"))
      (node (ref "U$5") (pin "P$2") (pinfunction "P$2_P$2") (pintype "bidirectional"))
      (node (ref "U$5") (pin "P$6") (pinfunction "P$6_P$6") (pintype "bidirectional"))
      (node (ref "U$5") (pin "TP") (pinfunction "P$6_TP") (pintype "bidirectional"))
      (node (ref "U1") (pin "1") (pinfunction "GND_1") (pintype "bidirectional"))
      (node (ref "U1") (pin "14") (pinfunction "GND_14") (pintype "bidirectional"))
      (node (ref "U1") (pin "20") (pinfunction "GND_20") (pintype "bidirectional"))
      (node (ref "U1") (pin "21") (pinfunction "GND_21") (pintype "bidirectional"))
      (node (ref "U1") (pin "22") (pinfunction "GND_22") (pintype "bidirectional"))
      (node (ref "U1") (pin "3") (pinfunction "GND_3") (pintype "bidirectional"))
      (node (ref "U1") (pin "30") (pinfunction "GND_30") (pintype "bidirectional"))
      (node (ref "U1") (pin "32") (pinfunction "GND65...96_32") (pintype "bidirectional"))
      (node (ref "U1") (pin "33") (pinfunction "RSVD_33") (pintype "bidirectional"))
      (node (ref "U1") (pin "43") (pinfunction "GND_43") (pintype "bidirectional"))
      (node (ref "U1") (pin "5") (pinfunction "GND_5") (pintype "bidirectional"))
      (node (ref "U1") (pin "50") (pinfunction "GND_50") (pintype "bidirectional"))
      (node (ref "U1") (pin "54") (pinfunction "GND_54") (pintype "bidirectional"))
      (node (ref "U1") (pin "55") (pinfunction "GND_55") (pintype "bidirectional"))
      (node (ref "U1") (pin "57") (pinfunction "GND_57") (pintype "bidirectional"))
      (node (ref "U1") (pin "58") (pinfunction "GND_58") (pintype "bidirectional"))
      (node (ref "U1") (pin "59") (pinfunction "GND_59") (pintype "bidirectional"))
      (node (ref "U1") (pin "60") (pinfunction "GND_60") (pintype "bidirectional"))
      (node (ref "U1") (pin "61") (pinfunction "GND_61") (pintype "bidirectional"))
      (node (ref "U1") (pin "63") (pinfunction "GND_63") (pintype "bidirectional"))
      (node (ref "U1") (pin "64") (pinfunction "GND_64") (pintype "bidirectional"))
      (node (ref "U1") (pin "65") (pinfunction "GND65...96_65") (pintype "bidirectional"))
      (node (ref "U1") (pin "66") (pinfunction "GND65...96_66") (pintype "bidirectional"))
      (node (ref "U1") (pin "67") (pinfunction "GND65...96_67") (pintype "bidirectional"))
      (node (ref "U1") (pin "68") (pinfunction "GND65...96_68") (pintype "bidirectional"))
      (node (ref "U1") (pin "69") (pinfunction "GND65...96_69") (pintype "bidirectional"))
      (node (ref "U1") (pin "70") (pinfunction "GND65...96_70") (pintype "bidirectional"))
      (node (ref "U1") (pin "71") (pinfunction "GND65...96_71") (pintype "bidirectional"))
      (node (ref "U1") (pin "72") (pinfunction "GND65...96_72") (pintype "bidirectional"))
      (node (ref "U1") (pin "73") (pinfunction "GND65...96_73") (pintype "bidirectional"))
      (node (ref "U1") (pin "74") (pinfunction "GND65...96_74") (pintype "bidirectional"))
      (node (ref "U1") (pin "75") (pinfunction "GND65...96_75") (pintype "bidirectional"))
      (node (ref "U1") (pin "76") (pinfunction "GND65...96_76") (pintype "bidirectional"))
      (node (ref "U1") (pin "77") (pinfunction "GND65...96_77") (pintype "bidirectional"))
      (node (ref "U1") (pin "78") (pinfunction "GND65...96_78") (pintype "bidirectional"))
      (node (ref "U1") (pin "79") (pinfunction "GND65...96_79") (pintype "bidirectional"))
      (node (ref "U1") (pin "80") (pinfunction "GND65...96_80") (pintype "bidirectional"))
      (node (ref "U1") (pin "81") (pinfunction "GND65...96_81") (pintype "bidirectional"))
      (node (ref "U1") (pin "82") (pinfunction "GND65...96_82") (pintype "bidirectional"))
      (node (ref "U1") (pin "83") (pinfunction "GND65...96_83") (pintype "bidirectional"))
      (node (ref "U1") (pin "84") (pinfunction "GND65...96_84") (pintype "bidirectional"))
      (node (ref "U1") (pin "85") (pinfunction "GND65...96_85") (pintype "bidirectional"))
      (node (ref "U1") (pin "86") (pinfunction "GND65...96_86") (pintype "bidirectional"))
      (node (ref "U1") (pin "87") (pinfunction "GND65...96_87") (pintype "bidirectional"))
      (node (ref "U1") (pin "88") (pinfunction "GND65...96_88") (pintype "bidirectional"))
      (node (ref "U1") (pin "89") (pinfunction "GND65...96_89") (pintype "bidirectional"))
      (node (ref "U1") (pin "9") (pinfunction "DTR_9") (pintype "bidirectional"))
      (node (ref "U1") (pin "90") (pinfunction "GND65...96_90") (pintype "bidirectional"))
      (node (ref "U1") (pin "91") (pinfunction "GND65...96_91") (pintype "bidirectional"))
      (node (ref "U1") (pin "92") (pinfunction "GND65...96_92") (pintype "bidirectional"))
      (node (ref "U1") (pin "93") (pinfunction "GND65...96_93") (pintype "bidirectional"))
      (node (ref "U1") (pin "94") (pinfunction "GND65...96_94") (pintype "bidirectional"))
      (node (ref "U1") (pin "95") (pinfunction "GND65...96_95") (pintype "bidirectional"))
      (node (ref "U1") (pin "96") (pinfunction "GND65...96_96") (pintype "bidirectional"))
      (node (ref "U2") (pin "10") (pinfunction "GND_10") (pintype "bidirectional"))
      (node (ref "U2") (pin "11") (pinfunction "GND_11") (pintype "bidirectional"))
      (node (ref "U3") (pin "12") (pinfunction "VSSA_12") (pintype "power_in"))
      (node (ref "U3") (pin "18") (pinfunction "VSS_4_18") (pintype "power_in"))
      (node (ref "U3") (pin "60") (pinfunction "BOOT0_60") (pintype "bidirectional"))
      (node (ref "U3") (pin "63") (pinfunction "VSS_3_63") (pintype "power_in"))
      (node (ref "U4") (pin "1") (pinfunction "CTG_1") (pintype "bidirectional"))
      (node (ref "U4") (pin "4") (pinfunction "GND_4") (pintype "bidirectional"))
      (node (ref "U4") (pin "6") (pinfunction "QST_6") (pintype "bidirectional"))
      (node (ref "U4") (pin "EP") (pinfunction "GND_EP") (pintype "bidirectional"))
      (node (ref "U5") (pin "3") (pinfunction "GND_3") (pintype "bidirectional"))
      (node (ref "U6") (pin "3") (pinfunction "GND_3") (pintype "bidirectional"))
      (node (ref "U8") (pin "10") (pinfunction "GND_10") (pintype "bidirectional"))
      (node (ref "U8") (pin "11") (pinfunction "GND_11") (pintype "bidirectional"))
      (node (ref "U8") (pin "4") (pinfunction "1DIR_4") (pintype "bidirectional"))
      (node (ref "U8") (pin "5") (pinfunction "2DIR_5") (pintype "bidirectional"))
      (node (ref "X1") (pin "GND") (pinfunction "GND_GND") (pintype "bidirectional"))
      (node (ref "X1") (pin "MT1") (pinfunction "GND_MT1") (pintype "bidirectional"))
      (node (ref "X1") (pin "MT2") (pinfunction "GND_MT2") (pintype "bidirectional"))
    )
    (net (code "37") (name "ILIM") (class "Default")
      (node (ref "R2") (pin "1") (pinfunction "1_1") (pintype "passive"))
      (node (ref "U$1") (pin "10") (pinfunction "ILIM_10") (pintype "output"))
    )
    (net (code "38") (name "LED1") (class "Default")
      (node (ref "BLUE_LED_0603") (pin "A") (pinfunction "A_A") (pintype "passive"))
      (node (ref "R10") (pin "1") (pinfunction "1_1") (pintype "passive"))
    )
    (net (code "39") (name "Net-(LED2-2)") (class "Default")
      (node (ref "LED2") (pin "BLUE") (pinfunction "2_BLUE") (pintype "passive"))
      (node (ref "R11") (pin "1") (pinfunction "1_1") (pintype "passive"))
    )
    (net (code "40") (name "Net-(LED2-3)") (class "Default")
      (node (ref "LED2") (pin "GREEN") (pinfunction "3_GREEN") (pintype "passive"))
      (node (ref "R9") (pin "1") (pinfunction "1_1") (pintype "passive"))
    )
    (net (code "41") (name "Net-(LED2-4)") (class "Default")
      (node (ref "LED2") (pin "RED") (pinfunction "4_RED") (pintype "passive"))
      (node (ref "R12") (pin "1") (pinfunction "1_1") (pintype "passive"))
    )
    (net (code "42") (name "Net-(R4-Pad2)") (class "Default")
      (node (ref "R4") (pin "2") (pinfunction "2_2") (pintype "passive"))
      (node (ref "RED_LED_0603") (pin "C") (pinfunction "C_C") (pintype "passive"))
    )
    (net (code "43") (name "Net-(U$1-INT)") (class "Default")
      (node (ref "R15") (pin "1") (pinfunction "1_1") (pintype "passive"))
      (node (ref "U$1") (pin "7") (pinfunction "INT_7") (pintype "bidirectional"))
    )
    (net (code "44") (name "Net-(U$1-OTG)") (class "Default")
      (node (ref "R16") (pin "1") (pinfunction "1_1") (pintype "passive"))
      (node (ref "U$1") (pin "8") (pinfunction "OTG_8") (pintype "bidirectional"))
    )
    (net (code "45") (name "Net-(U$1-TS)") (class "Default")
      (node (ref "R18") (pin "2") (pinfunction "2_2") (pintype "passive"))
      (node (ref "R19") (pin "1") (pinfunction "1_1") (pintype "passive"))
      (node (ref "R20") (pin "1") (pinfunction "1_1") (pintype "passive"))
      (node (ref "U$1") (pin "11") (pinfunction "TS_11") (pintype "bidirectional"))
    )
    (net (code "46") (name "Net-(U$1-~{PG})") (class "Default")
      (node (ref "R7") (pin "1") (pinfunction "1_1") (pintype "passive"))
      (node (ref "U$1") (pin "3") (pinfunction "~{PG}_3") (pintype "output"))
    )
    (net (code "47") (name "Net-(U$1-~{QON})") (class "Default")
      (node (ref "R20") (pin "2") (pinfunction "2_2") (pintype "passive"))
      (node (ref "U$1") (pin "12") (pinfunction "~{QON}_12") (pintype "bidirectional"))
    )
    (net (code "48") (name "Net-(U3-VCAP_1)") (class "Default")
      (node (ref "C35") (pin "1") (pinfunction "1_1") (pintype "passive"))
      (node (ref "U3") (pin "31") (pinfunction "VCAP_1_31") (pintype "power_in"))
    )
    (net (code "49") (name "Net-(U3-VCAP_2)") (class "Default")
      (node (ref "C32") (pin "1") (pinfunction "1_1") (pintype "passive"))
      (node (ref "U3") (pin "47") (pinfunction "VCAP_2_47") (pintype "power_in"))
    )
    (net (code "50") (name "Net-(U4-CELL)") (class "Default")
      (node (ref "C39") (pin "1") (pinfunction "1_1") (pintype "passive"))
      (node (ref "R23") (pin "1") (pinfunction "1_1") (pintype "passive"))
      (node (ref "U4") (pin "2") (pinfunction "CELL_2") (pintype "bidirectional"))
    )
    (net (code "51") (name "Net-(U4-VDD)") (class "Default")
      (node (ref "C38") (pin "1") (pinfunction "1_1") (pintype "passive"))
      (node (ref "R22") (pin "1") (pinfunction "1_1") (pintype "passive"))
      (node (ref "U4") (pin "3") (pinfunction "VDD_3") (pintype "bidirectional"))
    )
    (net (code "52") (name "OSC32_IN_UC") (class "Default")
      (node (ref "C34") (pin "1") (pinfunction "1_1") (pintype "passive"))
      (node (ref "U3") (pin "3") (pinfunction "PC14_3") (pintype "bidirectional"))
      (node (ref "Y1") (pin "X1") (pinfunction "1_X1") (pintype "passive"))
    )
    (net (code "53") (name "OSC32_OUT_UC") (class "Default")
      (node (ref "C33") (pin "1") (pinfunction "1_1") (pintype "passive"))
      (node (ref "U3") (pin "4") (pinfunction "PC15_4") (pintype "bidirectional"))
      (node (ref "Y1") (pin "X2") (pinfunction "2_X2") (pintype "passive"))
    )
    (net (code "54") (name "OSC_IN_UC") (class "Default")
      (node (ref "C28") (pin "1") (pinfunction "1_1") (pintype "passive"))
      (node (ref "U3") (pin "5") (pinfunction "PH0/OSC_IN_5") (pintype "bidirectional"))
      (node (ref "Y2") (pin "1") (pinfunction "1_1") (pintype "passive"))
    )
    (net (code "55") (name "OSC_OUT_UC") (class "Default")
      (node (ref "C26") (pin "1") (pinfunction "1_1") (pintype "passive"))
      (node (ref "U3") (pin "6") (pinfunction "PH1/OSC_OUT_6") (pintype "bidirectional"))
      (node (ref "Y2") (pin "3") (pinfunction "2_3") (pintype "passive"))
    )
    (net (code "56") (name "PA8_PM_SCL") (class "Default")
      (node (ref "R14") (pin "1") (pinfunction "1_1") (pintype "passive"))
      (node (ref "U$1") (pin "5") (pinfunction "SCL_5") (pintype "output"))
      (node (ref "U3") (pin "41") (pinfunction "PA8_41") (pintype "bidirectional"))
      (node (ref "U4") (pin "7") (pinfunction "SCL_7") (pintype "bidirectional"))
    )
    (net (code "57") (name "PC9_PM_SDA") (class "Default")
      (node (ref "R13") (pin "1") (pinfunction "1_1") (pintype "passive"))
      (node (ref "U$1") (pin "6") (pinfunction "SDA_6") (pintype "bidirectional"))
      (node (ref "U3") (pin "40") (pinfunction "PC9_40") (pintype "bidirectional"))
      (node (ref "U4") (pin "8") (pinfunction "SDA_8") (pintype "bidirectional"))
    )
    (net (code "58") (name "PMID") (class "Default")
      (node (ref "C5") (pin "1") (pinfunction "1_1") (pintype "passive"))
      (node (ref "JP3") (pin "1") (pinfunction "1_1") (pintype "passive"))
      (node (ref "U$1") (pin "23") (pinfunction "PMID_23") (pintype "passive"))
    )
    (net (code "59") (name "PWR_UB") (class "Default")
      (node (ref "R1") (pin "1") (pinfunction "1_1") (pintype "passive"))
      (node (ref "U1") (pin "15") (pinfunction "PWR_ON_15") (pintype "bidirectional"))
      (node (ref "U5") (pin "4") (pinfunction "B_4") (pintype "bidirectional"))
    )
    (net (code "60") (name "PWR_UC") (class "Default")
      (node (ref "U3") (pin "28") (pinfunction "PB2_28") (pintype "bidirectional"))
      (node (ref "U5") (pin "2") (pinfunction "A_2") (pintype "bidirectional"))
    )
    (net (code "61") (name "REGN") (class "Default")
      (node (ref "C25") (pin "1") (pinfunction "1_1") (pintype "passive"))
      (node (ref "R18") (pin "1") (pinfunction "1_1") (pintype "passive"))
      (node (ref "U$1") (pin "22") (pinfunction "REGN_22") (pintype "bidirectional"))
    )
    (net (code "62") (name "RESET_UB") (class "Default")
      (node (ref "U1") (pin "18") (pinfunction "RESET_N_18") (pintype "bidirectional"))
      (node (ref "U6") (pin "4") (pinfunction "B_4") (pintype "bidirectional"))
    )
    (net (code "63") (name "RESET_UC") (class "Default")
      (node (ref "U3") (pin "24") (pinfunction "PC4_24") (pintype "bidirectional"))
      (node (ref "U6") (pin "2") (pinfunction "A_2") (pintype "bidirectional"))
    )
    (net (code "64") (name "RGB_BLUE") (class "Default")
      (node (ref "R11") (pin "2") (pinfunction "2_2") (pintype "passive"))
      (node (ref "U3") (pin "17") (pinfunction "PA3_17") (pintype "bidirectional"))
    )
    (net (code "65") (name "RGB_GREEN") (class "Default")
      (node (ref "R9") (pin "2") (pinfunction "2_2") (pintype "passive"))
      (node (ref "U3") (pin "16") (pinfunction "PA2_16") (pintype "bidirectional"))
    )
    (net (code "66") (name "RGB_RED") (class "Default")
      (node (ref "R12") (pin "2") (pinfunction "2_2") (pintype "passive"))
      (node (ref "U3") (pin "15") (pinfunction "PA1_15") (pintype "bidirectional"))
    )
    (net (code "67") (name "RI_UB") (class "Default")
      (node (ref "U1") (pin "7") (pinfunction "RI_7") (pintype "bidirectional"))
      (node (ref "U8") (pin "14") (pinfunction "1B2_14") (pintype "bidirectional"))
    )
    (net (code "68") (name "RI_UC") (class "Default")
      (node (ref "U3") (pin "33") (pinfunction "PB12_33") (pintype "bidirectional"))
      (node (ref "U8") (pin "7") (pinfunction "1A2_7") (pintype "bidirectional"))
    )
    (net (code "69") (name "RTS_UB") (class "Default")
      (node (ref "U1") (pin "10") (pinfunction "RTS_10") (pintype "bidirectional"))
      (node (ref "U2") (pin "15") (pinfunction "1B1_15") (pintype "bidirectional"))
    )
    (net (code "70") (name "RTS_UC") (class "Default")
      (node (ref "U2") (pin "6") (pinfunction "1A1_6") (pintype "bidirectional"))
      (node (ref "U3") (pin "35") (pinfunction "PB14_35") (pintype "bidirectional"))
    )
    (net (code "71") (name "RX") (class "Default")
      (node (ref "JP1") (pin "4") (pinfunction "4_4") (pintype "passive"))
      (node (ref "U3") (pin "43") (pinfunction "PA10_43") (pintype "bidirectional"))
    )
    (net (code "72") (name "RXD_UB") (class "Default")
      (node (ref "U1") (pin "13") (pinfunction "RXD_13") (pintype "bidirectional"))
      (node (ref "U8") (pin "13") (pinfunction "2B1_13") (pintype "bidirectional"))
    )
    (net (code "73") (name "RXD_UC") (class "Default")
      (node (ref "U3") (pin "30") (pinfunction "PB11_30") (pintype "bidirectional"))
      (node (ref "U8") (pin "8") (pinfunction "2A1_8") (pintype "bidirectional"))
    )
    (net (code "74") (name "SIM_CLK") (class "Default")
      (node (ref "C12") (pin "1") (pinfunction "1_1") (pintype "passive"))
      (node (ref "J1") (pin "C3") (pinfunction "CLK_C3") (pintype "passive"))
      (node (ref "U1") (pin "38") (pinfunction "SIM_CLK_38") (pintype "bidirectional"))
    )
    (net (code "75") (name "SIM_DET") (class "Default")
      (node (ref "U1") (pin "42") (pinfunction "SIM_DET_42") (pintype "bidirectional"))
    )
    (net (code "76") (name "SIM_IO") (class "Default")
      (node (ref "C13") (pin "1") (pinfunction "1_1") (pintype "passive"))
      (node (ref "J1") (pin "C7") (pinfunction "I/O_C7") (pintype "passive"))
      (node (ref "U1") (pin "39") (pinfunction "SIM_IO_39") (pintype "bidirectional"))
    )
    (net (code "77") (name "SIM_RST") (class "Default")
      (node (ref "C10") (pin "1") (pinfunction "1_1") (pintype "passive"))
      (node (ref "J1") (pin "C2") (pinfunction "RST_C2") (pintype "passive"))
      (node (ref "U1") (pin "40") (pinfunction "SIM_RST_40") (pintype "bidirectional"))
    )
    (net (code "78") (name "SIM_VCC") (class "Default")
      (node (ref "C11") (pin "1") (pinfunction "1_1") (pintype "passive"))
      (node (ref "C14") (pin "1") (pinfunction "1_1") (pintype "passive"))
      (node (ref "J1") (pin "C1") (pinfunction "VCC_C1") (pintype "passive"))
      (node (ref "J1") (pin "C6") (pinfunction "VPP_C6") (pintype "passive"))
      (node (ref "U1") (pin "41") (pinfunction "VSIM_41") (pintype "bidirectional"))
    )
    (net (code "79") (name "STAT") (class "Default")
      (node (ref "R4") (pin "1") (pinfunction "1_1") (pintype "passive"))
      (node (ref "U$1") (pin "4") (pinfunction "STAT_4") (pintype "bidirectional"))
    )
    (net (code "80") (name "SW1") (class "Default")
      (node (ref "C7") (pin "2") (pinfunction "2_2") (pintype "passive"))
      (node (ref "U$1") (pin "19") (pinfunction "SW_19") (pintype "power_in"))
      (node (ref "U$1") (pin "20") (pinfunction "SW_20") (pintype "power_in"))
      (node (ref "U$4") (pin "P$1") (pinfunction "1_P$1") (pintype "passive"))
    )
    (net (code "81") (name "SW2") (class "Default")
      (node (ref "U$5") (pin "P$1") (pinfunction "P$1_P$1") (pintype "bidirectional"))
      (node (ref "U$6") (pin "1") (pinfunction "1_1") (pintype "passive"))
    )
    (net (code "82") (name "TX") (class "Default")
      (node (ref "JP1") (pin "3") (pinfunction "3_3") (pintype "passive"))
      (node (ref "U3") (pin "42") (pinfunction "PA9_42") (pintype "bidirectional"))
    )
    (net (code "83") (name "TXD_UB") (class "Default")
      (node (ref "U1") (pin "12") (pinfunction "TXD_12") (pintype "bidirectional"))
      (node (ref "U2") (pin "14") (pinfunction "1B2_14") (pintype "bidirectional"))
    )
    (net (code "84") (name "TXD_UC") (class "Default")
      (node (ref "U2") (pin "7") (pinfunction "1A2_7") (pintype "bidirectional"))
      (node (ref "U3") (pin "29") (pinfunction "PB10_29") (pintype "bidirectional"))
    )
    (net (code "85") (name "USB_DM") (class "Default")
      (node (ref "R6") (pin "2") (pinfunction "2_2") (pintype "passive"))
      (node (ref "R7") (pin "2") (pinfunction "2_2") (pintype "passive"))
      (node (ref "U$7") (pin "P$2") (pinfunction "P$2_P$2") (pintype "bidirectional"))
      (node (ref "X1") (pin "D-") (pinfunction "D-_D-") (pintype "bidirectional"))
    )
    (net (code "86") (name "USB_DM_UC") (class "Default")
      (node (ref "R6") (pin "1") (pinfunction "1_1") (pintype "passive"))
      (node (ref "U3") (pin "44") (pinfunction "PA11_44") (pintype "bidirectional"))
    )
    (net (code "87") (name "USB_DP") (class "Default")
      (node (ref "R5") (pin "2") (pinfunction "2_2") (pintype "passive"))
      (node (ref "U$1") (pin "2") (pinfunction "PSEL_2") (pintype "output"))
      (node (ref "U$7") (pin "P$1") (pinfunction "P$1_P$1") (pintype "bidirectional"))
      (node (ref "X1") (pin "D+") (pinfunction "D+_D+") (pintype "bidirectional"))
    )
    (net (code "88") (name "USB_DP_UC") (class "Default")
      (node (ref "R5") (pin "1") (pinfunction "1_1") (pintype "passive"))
      (node (ref "U3") (pin "45") (pinfunction "PA12_45") (pintype "bidirectional"))
    )
    (net (code "89") (name "VBAT") (class "Default")
      (node (ref "JP2") (pin "16") (pinfunction "16_16") (pintype "passive"))
      (node (ref "U3") (pin "1") (pinfunction "VBAT_1") (pintype "power_in"))
    )
    (net (code "90") (name "VBUS") (class "Default")
      (node (ref "U$3") (pin "ANODE") (pinfunction "ANODE_ANODE") (pintype "bidirectional"))
      (node (ref "X1") (pin "VBUS") (pinfunction "VBUS_VBUS") (pintype "bidirectional"))
    )
    (net (code "91") (name "VIN") (class "Default")
      (node (ref "C4") (pin "1") (pinfunction "1_1") (pintype "passive"))
      (node (ref "JP1") (pin "1") (pinfunction "1_1") (pintype "passive"))
      (node (ref "U$1") (pin "1") (pinfunction "VBUS_1") (pintype "power_in"))
      (node (ref "U$1") (pin "24") (pinfunction "VBUS_24") (pintype "passive"))
      (node (ref "U$3") (pin "CATHODE") (pinfunction "CATHODE_CATHODE") (pintype "bidirectional"))
    )
    (net (code "92") (name "V_BCKP") (class "Default")
      (node (ref "R1") (pin "2") (pinfunction "2_2") (pintype "passive"))
      (node (ref "U1") (pin "2") (pinfunction "V_BCKP_2") (pintype "bidirectional"))
    )
    (net (code "93") (name "V_INT") (class "Default")
      (node (ref "C21") (pin "1") (pinfunction "1_1") (pintype "passive"))
      (node (ref "C22") (pin "1") (pinfunction "1_1") (pintype "passive"))
      (node (ref "U1") (pin "4") (pinfunction "V_INT_4") (pintype "bidirectional"))
      (node (ref "U2") (pin "2") (pinfunction "VCCB_2") (pintype "bidirectional"))
      (node (ref "U8") (pin "2") (pinfunction "VCCB_2") (pintype "bidirectional"))
    )
    (net (code "94") (name "WKP") (class "Default")
      (node (ref "JP1") (pin "5") (pinfunction "5_5") (pintype "passive"))
      (node (ref "U3") (pin "14") (pinfunction "WKUP/PA0_14") (pintype "bidirectional"))
    )
    (net (code "95") (name "unconnected-(MODE-Pad4)") (class "Default")
      (node (ref "MODE") (pin "4") (pinfunction "4_4") (pintype "passive"))
    )
    (net (code "96") (name "unconnected-(RESET-Pad1)") (class "Default")
      (node (ref "RESET") (pin "1") (pinfunction "1_1") (pintype "passive"))
    )
    (net (code "97") (name "unconnected-(U1-DCD-Pad8)") (class "Default")
      (node (ref "U1") (pin "8") (pinfunction "DCD_8") (pintype "bidirectional"))
    )
    (net (code "98") (name "unconnected-(U1-DSR-Pad6)") (class "Default")
      (node (ref "U1") (pin "6") (pinfunction "DSR_6") (pintype "bidirectional"))
    )
    (net (code "99") (name "unconnected-(U1-GPIO1-Pad16)") (class "Default")
      (node (ref "U1") (pin "16") (pinfunction "GPIO1_16") (pintype "bidirectional"))
    )
    (net (code "100") (name "unconnected-(U1-GPIO2-Pad23)") (class "Default")
      (node (ref "U1") (pin "23") (pinfunction "GPIO2_23") (pintype "bidirectional"))
    )
    (net (code "101") (name "unconnected-(U1-GPIO3-Pad24)") (class "Default")
      (node (ref "U1") (pin "24") (pinfunction "GPIO3_24") (pintype "bidirectional"))
    )
    (net (code "102") (name "unconnected-(U1-GPIO4-Pad25)") (class "Default")
      (node (ref "U1") (pin "25") (pinfunction "GPIO4_25") (pintype "bidirectional"))
    )
    (net (code "103") (name "unconnected-(U1-I2S_CLK-Pad36)") (class "Default")
      (node (ref "U1") (pin "36") (pinfunction "I2S_CLK_36") (pintype "bidirectional"))
    )
    (net (code "104") (name "unconnected-(U1-I2S_RXD-Pad37)") (class "Default")
      (node (ref "U1") (pin "37") (pinfunction "I2S_RXD_37") (pintype "bidirectional"))
    )
    (net (code "105") (name "unconnected-(U1-I2S_TXD-Pad35)") (class "Default")
      (node (ref "U1") (pin "35") (pinfunction "I2S_TXD_35") (pintype "bidirectional"))
    )
    (net (code "106") (name "unconnected-(U1-I2S_WA-Pad34)") (class "Default")
      (node (ref "U1") (pin "34") (pinfunction "I2S_WA_34") (pintype "bidirectional"))
    )
    (net (code "107") (name "unconnected-(U1-MIC_BIAS-Pad46)") (class "Default")
      (node (ref "U1") (pin "46") (pinfunction "MIC_BIAS_46") (pintype "bidirectional"))
    )
    (net (code "108") (name "unconnected-(U1-MIC_GND-Pad47)") (class "Default")
      (node (ref "U1") (pin "47") (pinfunction "MIC_GND_47") (pintype "bidirectional"))
    )
    (net (code "109") (name "unconnected-(U1-MIC_N-Pad48)") (class "Default")
      (node (ref "U1") (pin "48") (pinfunction "MIC_N_48") (pintype "bidirectional"))
    )
    (net (code "110") (name "unconnected-(U1-MIC_P-Pad49)") (class "Default")
      (node (ref "U1") (pin "49") (pinfunction "MIC_P_49") (pintype "bidirectional"))
    )
    (net (code "111") (name "unconnected-(U1-RSVD-Pad19)") (class "Default")
      (node (ref "U1") (pin "19") (pinfunction "RSVD_19") (pintype "bidirectional"))
    )
    (net (code "112") (name "unconnected-(U1-RSVD-Pad31)") (class "Default")
      (node (ref "U1") (pin "31") (pinfunction "RSVD_31") (pintype "bidirectional"))
    )
    (net (code "113") (name "unconnected-(U1-RXD_AUX{slash}USB_D--Pad28)") (class "Default")
      (node (ref "U1") (pin "28") (pinfunction "RXD_AUX/USB_D-_28") (pintype "bidirectional"))
    )
    (net (code "114") (name "unconnected-(U1-SCL-Pad27)") (class "Default")
      (node (ref "U1") (pin "27") (pinfunction "SCL_27") (pintype "bidirectional"))
    )
    (net (code "115") (name "unconnected-(U1-SDA-Pad26)") (class "Default")
      (node (ref "U1") (pin "26") (pinfunction "SDA_26") (pintype "bidirectional"))
    )
    (net (code "116") (name "unconnected-(U1-SPK_N-Pad45)") (class "Default")
      (node (ref "U1") (pin "45") (pinfunction "SPK_N_45") (pintype "bidirectional"))
    )
    (net (code "117") (name "unconnected-(U1-SPK_P-Pad44)") (class "Default")
      (node (ref "U1") (pin "44") (pinfunction "SPK_P_44") (pintype "bidirectional"))
    )
    (net (code "118") (name "unconnected-(U1-TXD_AUX{slash}USB_D+-Pad29)") (class "Default")
      (node (ref "U1") (pin "29") (pinfunction "TXD_AUX/USB_D+_29") (pintype "bidirectional"))
    )
    (net (code "119") (name "unconnected-(U1-VUSB_DET-Pad17)") (class "Default")
      (node (ref "U1") (pin "17") (pinfunction "VUSB_DET_17") (pintype "bidirectional"))
    )
    (net (code "120") (name "unconnected-(U2-2A1-Pad8)") (class "Default")
      (node (ref "U2") (pin "8") (pinfunction "2A1_8") (pintype "bidirectional"))
    )
    (net (code "121") (name "unconnected-(U2-2A2-Pad9)") (class "Default")
      (node (ref "U2") (pin "9") (pinfunction "2A2_9") (pintype "bidirectional"))
    )
    (net (code "122") (name "unconnected-(U2-2B1-Pad13)") (class "Default")
      (node (ref "U2") (pin "13") (pinfunction "2B1_13") (pintype "bidirectional"))
    )
    (net (code "123") (name "unconnected-(U2-2B2-Pad12)") (class "Default")
      (node (ref "U2") (pin "12") (pinfunction "2B2_12") (pintype "bidirectional"))
    )
    (net (code "124") (name "unconnected-(U8-2A2-Pad9)") (class "Default")
      (node (ref "U8") (pin "9") (pinfunction "2A2_9") (pintype "bidirectional"))
    )
    (net (code "125") (name "unconnected-(U8-2B2-Pad12)") (class "Default")
      (node (ref "U8") (pin "12") (pinfunction "2B2_12") (pintype "bidirectional"))
    )
    (net (code "126") (name "~{CE}") (class "Default")
      (node (ref "R17") (pin "1") (pinfunction "1_1") (pintype "passive"))
      (node (ref "U$1") (pin "9") (pinfunction "~{CE}_9") (pintype "output"))
    )
    (net (code "127") (name "~{LOW_BAT_INT_UC}") (class "Default")
      (node (ref "R21") (pin "1") (pinfunction "1_1") (pintype "passive"))
      (node (ref "U3") (pin "2") (pinfunction "PC13_2") (pintype "bidirectional"))
      (node (ref "U4") (pin "5") (pinfunction "ALT_5") (pintype "bidirectional"))
    )
    (net (code "128") (name "~{LVLOE_UC}") (class "Default")
      (node (ref "R3") (pin "1") (pinfunction "1_1") (pintype "passive"))
      (node (ref "U2") (pin "1") (pinfunction "1/OE_1") (pintype "bidirectional"))
      (node (ref "U2") (pin "16") (pinfunction "2/OE_16") (pintype "bidirectional"))
      (node (ref "U3") (pin "36") (pinfunction "PB15_36") (pintype "bidirectional"))
      (node (ref "U8") (pin "1") (pinfunction "1/OE_1") (pintype "bidirectional"))
      (node (ref "U8") (pin "16") (pinfunction "2/OE_16") (pintype "bidirectional"))
    )
    (net (code "129") (name "~{MODE}") (class "Default")
      (node (ref "MODE") (pin "3") (pinfunction "3_3") (pintype "passive"))
      (node (ref "U3") (pin "38") (pinfunction "PC7_38") (pintype "bidirectional"))
    )
    (net (code "130") (name "~{RST}") (class "Default")
      (node (ref "C6") (pin "1") (pinfunction "1_1") (pintype "passive"))
      (node (ref "JP2") (pin "17") (pinfunction "17_17") (pintype "passive"))
      (node (ref "R8") (pin "1") (pinfunction "1_1") (pintype "passive"))
      (node (ref "RESET") (pin "2") (pinfunction "2_2") (pintype "passive"))
      (node (ref "U3") (pin "7") (pinfunction "NRST_7") (pintype "power_in"))
    )
  )
)
